# PSUBoard.net
KiCad netlist of a schematic drawn in EAGLE
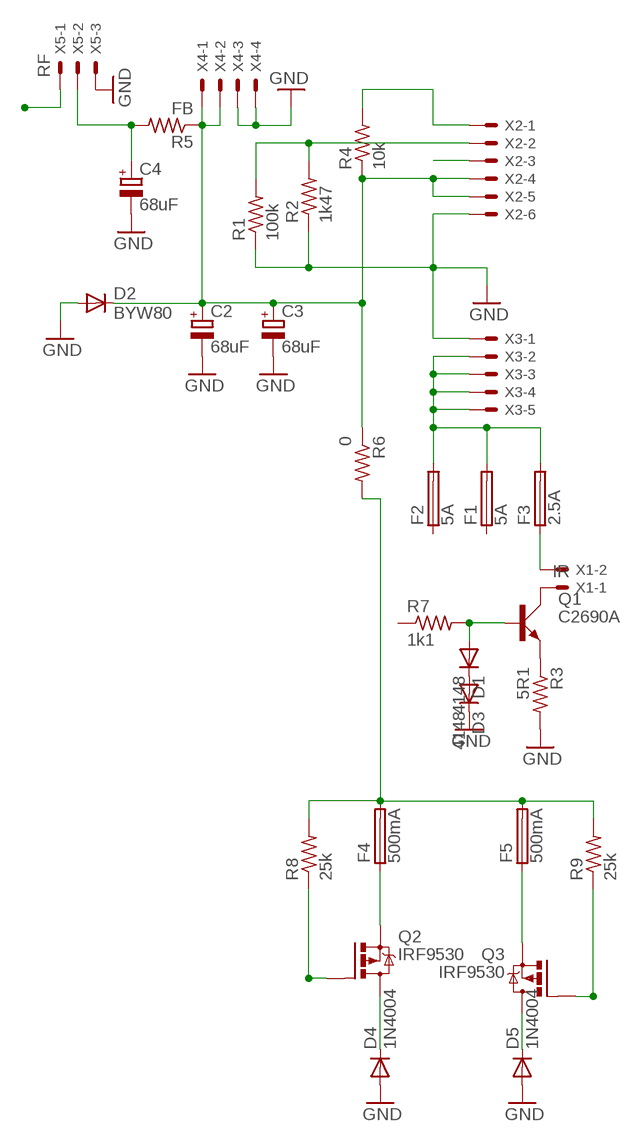
[diagram p0: schematic, sheet 1]

(export (version "E")
  (design (tool "Eeschema 10.0.6"))
  (components
    (comp (ref "C2")
      (value "68uF")
      (footprint "eagle-import:E3,5-10")
      (libsource (lib "eagle-import") (part "CPOL-EUE3.5-10"))
    )
    (comp (ref "C3")
      (value "68uF")
      (footprint "eagle-import:E3,5-10")
      (libsource (lib "eagle-import") (part "CPOL-EUE3.5-10"))
    )
    (comp (ref "C4")
      (value "68uF")
      (footprint "eagle-import:E3,5-10")
      (libsource (lib "eagle-import") (part "CPOL-EUE3.5-10"))
    )
    (comp (ref "D1")
      (value "4148")
      (footprint "eagle-import:DO35-7")
      (libsource (lib "eagle-import") (part "1N4148DO35-7"))
    )
    (comp (ref "D2")
      (value "BYW80")
      (footprint "eagle-import:TO220ACS")
      (libsource (lib "eagle-import") (part "BYW80"))
    )
    (comp (ref "D3")
      (value "4148")
      (footprint "eagle-import:DO35-7")
      (libsource (lib "eagle-import") (part "1N4148DO35-7"))
    )
    (comp (ref "D4")
      (value "1N4004")
      (footprint "eagle-import:DO41-10")
      (libsource (lib "eagle-import") (part "1N4004"))
    )
    (comp (ref "D5")
      (value "1N4004")
      (footprint "eagle-import:DO41-10")
      (libsource (lib "eagle-import") (part "1N4004"))
    )
    (comp (ref "F1")
      (value "5A")
      (footprint "eagle-import:TR5")
      (libsource (lib "eagle-import") (part "TR5"))
    )
    (comp (ref "F2")
      (value "5A")
      (footprint "eagle-import:TR5")
      (libsource (lib "eagle-import") (part "TR5"))
    )
    (comp (ref "F3")
      (value "2.5A")
      (footprint "eagle-import:TR5")
      (libsource (lib "eagle-import") (part "TR5"))
    )
    (comp (ref "F4")
      (value "500mA")
      (footprint "eagle-import:TR5")
      (libsource (lib "eagle-import") (part "TR5"))
    )
    (comp (ref "F5")
      (value "500mA")
      (footprint "eagle-import:TR5")
      (libsource (lib "eagle-import") (part "TR5"))
    )
    (comp (ref "Q1")
      (value "C2690A")
      (footprint "eagle-import:TO126AV")
      (libsource (lib "eagle-import") (part "BD139"))
    )
    (comp (ref "Q2")
      (value "IRF9530")
      (footprint "eagle-import:TO220BV")
      (libsource (lib "eagle-import") (part "IRF9530"))
    )
    (comp (ref "Q3")
      (value "IRF9530")
      (footprint "eagle-import:TO220BV")
      (libsource (lib "eagle-import") (part "IRF9530"))
    )
    (comp (ref "R1")
      (value "100k")
      (footprint "eagle-import:0309_12")
      (libsource (lib "eagle-import") (part "R-US_0309/12"))
    )
    (comp (ref "R2")
      (value "1k47")
      (footprint "eagle-import:0617_22")
      (libsource (lib "eagle-import") (part "R-US_0617/22"))
    )
    (comp (ref "R3")
      (value "5R1")
      (footprint "eagle-import:0309_10")
      (libsource (lib "eagle-import") (part "R-US_0309/10"))
    )
    (comp (ref "R4")
      (value "10k")
      (footprint "eagle-import:0309_12")
      (libsource (lib "eagle-import") (part "R-US_0309/12"))
    )
    (comp (ref "R5")
      (value "FB")
      (footprint "eagle-import:0309_12")
      (libsource (lib "eagle-import") (part "R-US_0309/12"))
    )
    (comp (ref "R6")
      (value "0")
      (footprint "eagle-import:0309_12")
      (libsource (lib "eagle-import") (part "R-US_0309/12"))
    )
    (comp (ref "R7")
      (value "1k1")
      (footprint "eagle-import:0309_10")
      (libsource (lib "eagle-import") (part "R-US_0309/10"))
    )
    (comp (ref "R8")
      (value "25k")
      (footprint "eagle-import:0309_10")
      (libsource (lib "eagle-import") (part "R-US_0309/10"))
    )
    (comp (ref "R9")
      (value "25k")
      (footprint "eagle-import:0309_10")
      (libsource (lib "eagle-import") (part "R-US_0309/10"))
    )
    (comp (ref "X1")
      (value "IR")
      (footprint "eagle-import:22-23-2021")
      (fields (field (name "MF") "MOLEX") (field (name "MPN") "22-23-2021"))
      (libsource (lib "eagle-import") (part "22-23-2021"))
    )
    (comp (ref "X2")
      (value "22-23-2061")
      (footprint "eagle-import:22-23-2061")
      (fields (field (name "MF") "MOLEX"))
      (libsource (lib "eagle-import") (part "22-23-2061"))
    )
    (comp (ref "X3")
      (value "22-23-2051")
      (footprint "eagle-import:22-23-2051")
      (fields (field (name "MF") "MOLEX"))
      (libsource (lib "eagle-import") (part "22-23-2051"))
    )
    (comp (ref "X4")
      (value "22-23-2041")
      (footprint "eagle-import:22-23-2041")
      (fields (field (name "MF") "MOLEX"))
      (libsource (lib "eagle-import") (part "22-23-2041"))
    )
    (comp (ref "X5")
      (value "RF")
      (footprint "eagle-import:22-23-2031")
      (fields (field (name "MF") "MOLEX") (field (name "MPN") "22-23-2031"))
      (libsource (lib "eagle-import") (part "22-23-2031"))
    )
  )
  (nets
    (net (code "1") (name "GND") (class "Default")
      (node (ref "C2") (pin "-") (pinfunction "-_-") (pintype "passive"))
      (node (ref "C3") (pin "-") (pinfunction "-_-") (pintype "passive"))
      (node (ref "C4") (pin "-") (pinfunction "-_-") (pintype "passive"))
      (node (ref "D2") (pin "A") (pinfunction "A_A") (pintype "passive"))
      (node (ref "D3") (pin "C") (pinfunction "C_C") (pintype "passive"))
      (node (ref "D4") (pin "A") (pinfunction "A_A") (pintype "passive"))
      (node (ref "D5") (pin "A") (pinfunction "A_A") (pintype "passive"))
      (node (ref "R1") (pin "1") (pinfunction "1_1") (pintype "passive"))
      (node (ref "R2") (pin "1") (pinfunction "1_1") (pintype "passive"))
      (node (ref "R3") (pin "2") (pinfunction "2_2") (pintype "passive"))
      (node (ref "X2") (pin "6") (pinfunction "S_6") (pintype "passive"))
      (node (ref "X3") (pin "1") (pinfunction "S_1") (pintype "passive"))
      (node (ref "X4") (pin "3") (pinfunction "S_3") (pintype "passive"))
      (node (ref "X4") (pin "4") (pinfunction "S_4") (pintype "passive"))
      (node (ref "X5") (pin "3") (pinfunction "S_3") (pintype "passive"))
    )
    (net (code "2") (name "Net-(D1-PadA)") (class "Default")
      (node (ref "D1") (pin "A") (pinfunction "A_A") (pintype "passive"))
      (node (ref "Q1") (pin "B") (pinfunction "B_B") (pintype "passive"))
      (node (ref "R7") (pin "2") (pinfunction "2_2") (pintype "passive"))
    )
    (net (code "3") (name "Net-(D1-PadC)") (class "Default")
      (node (ref "D1") (pin "C") (pinfunction "C_C") (pintype "passive"))
      (node (ref "D3") (pin "A") (pinfunction "A_A") (pintype "passive"))
    )
    (net (code "4") (name "Net-(D4-PadC)") (class "Default")
      (node (ref "D4") (pin "C") (pinfunction "C_C") (pintype "passive"))
      (node (ref "Q2") (pin "D") (pinfunction "D_D") (pintype "passive"))
    )
    (net (code "5") (name "Net-(D5-PadC)") (class "Default")
      (node (ref "D5") (pin "C") (pinfunction "C_C") (pintype "passive"))
      (node (ref "Q3") (pin "D") (pinfunction "D_D") (pintype "passive"))
    )
    (net (code "6") (name "Net-(F4-Pad1)") (class "Default")
      (node (ref "F4") (pin "1") (pinfunction "1_1") (pintype "passive"))
      (node (ref "Q2") (pin "S") (pinfunction "S_S") (pintype "passive"))
    )
    (net (code "7") (name "Net-(F4-Pad2)") (class "Default")
      (node (ref "F4") (pin "2") (pinfunction "2_2") (pintype "passive"))
      (node (ref "F5") (pin "2") (pinfunction "2_2") (pintype "passive"))
      (node (ref "R6") (pin "2") (pinfunction "2_2") (pintype "passive"))
      (node (ref "R8") (pin "2") (pinfunction "2_2") (pintype "passive"))
      (node (ref "R9") (pin "2") (pinfunction "2_2") (pintype "passive"))
    )
    (net (code "8") (name "Net-(F5-Pad1)") (class "Default")
      (node (ref "F5") (pin "1") (pinfunction "1_1") (pintype "passive"))
      (node (ref "Q3") (pin "S") (pinfunction "S_S") (pintype "passive"))
    )
    (net (code "9") (name "Net-(Q1-PadE)") (class "Default")
      (node (ref "Q1") (pin "E") (pinfunction "E_E") (pintype "passive"))
      (node (ref "R3") (pin "1") (pinfunction "1_1") (pintype "passive"))
    )
    (net (code "10") (name "Net-(Q2-PadG)") (class "Default")
      (node (ref "Q2") (pin "G") (pinfunction "G_G") (pintype "passive"))
      (node (ref "R8") (pin "1") (pinfunction "1_1") (pintype "passive"))
    )
    (net (code "11") (name "Net-(Q3-PadG)") (class "Default")
      (node (ref "Q3") (pin "G") (pinfunction "G_G") (pintype "passive"))
      (node (ref "R9") (pin "1") (pinfunction "1_1") (pintype "passive"))
    )
    (net (code "12") (name "Net-(X1A-S)") (class "Default")
      (node (ref "Q1") (pin "C") (pinfunction "C_C") (pintype "passive"))
      (node (ref "X1") (pin "1") (pinfunction "S_1") (pintype "passive"))
    )
    (net (code "13") (name "Net-(X1B-S)") (class "Default")
      (node (ref "F3") (pin "1") (pinfunction "1_1") (pintype "passive"))
      (node (ref "X1") (pin "2") (pinfunction "S_2") (pintype "passive"))
    )
    (net (code "14") (name "Net-(X2A-S)") (class "Default")
      (node (ref "R4") (pin "2") (pinfunction "2_2") (pintype "passive"))
      (node (ref "X2") (pin "1") (pinfunction "S_1") (pintype "passive"))
    )
    (net (code "15") (name "Net-(X2B-S)") (class "Default")
      (node (ref "R1") (pin "2") (pinfunction "2_2") (pintype "passive"))
      (node (ref "R2") (pin "2") (pinfunction "2_2") (pintype "passive"))
      (node (ref "X2") (pin "2") (pinfunction "S_2") (pintype "passive"))
    )
    (net (code "16") (name "Net-(X2D-S)") (class "Default")
      (node (ref "C2") (pin "+") (pinfunction "+_+") (pintype "passive"))
      (node (ref "C3") (pin "+") (pinfunction "+_+") (pintype "passive"))
      (node (ref "D2") (pin "C") (pinfunction "C_C") (pintype "passive"))
      (node (ref "R4") (pin "1") (pinfunction "1_1") (pintype "passive"))
      (node (ref "R5") (pin "1") (pinfunction "1_1") (pintype "passive"))
      (node (ref "R6") (pin "1") (pinfunction "1_1") (pintype "passive"))
      (node (ref "X2") (pin "4") (pinfunction "S_4") (pintype "passive"))
      (node (ref "X2") (pin "5") (pinfunction "S_5") (pintype "passive"))
      (node (ref "X4") (pin "1") (pinfunction "S_1") (pintype "passive"))
      (node (ref "X4") (pin "2") (pinfunction "S_2") (pintype "passive"))
    )
    (net (code "17") (name "Net-(X3B-S)") (class "Default")
      (node (ref "F1") (pin "2") (pinfunction "2_2") (pintype "passive"))
      (node (ref "F2") (pin "2") (pinfunction "2_2") (pintype "passive"))
      (node (ref "F3") (pin "2") (pinfunction "2_2") (pintype "passive"))
      (node (ref "X3") (pin "2") (pinfunction "S_2") (pintype "passive"))
      (node (ref "X3") (pin "3") (pinfunction "S_3") (pintype "passive"))
      (node (ref "X3") (pin "4") (pinfunction "S_4") (pintype "passive"))
      (node (ref "X3") (pin "5") (pinfunction "S_5") (pintype "passive"))
    )
    (net (code "18") (name "Net-(X5B-S)") (class "Default")
      (node (ref "C4") (pin "+") (pinfunction "+_+") (pintype "passive"))
      (node (ref "R5") (pin "2") (pinfunction "2_2") (pintype "passive"))
      (node (ref "X5") (pin "2") (pinfunction "S_2") (pintype "passive"))
    )
    (net (code "19") (name "unconnected-(F1-Pad1)") (class "Default")
      (node (ref "F1") (pin "1") (pinfunction "1_1") (pintype "passive"))
    )
    (net (code "20") (name "unconnected-(F2-Pad1)") (class "Default")
      (node (ref "F2") (pin "1") (pinfunction "1_1") (pintype "passive"))
    )
    (net (code "21") (name "unconnected-(R7-Pad1)") (class "Default")
      (node (ref "R7") (pin "1") (pinfunction "1_1") (pintype "passive"))
    )
    (net (code "22") (name "unconnected-(X2C-S-Pad3)") (class "Default")
      (node (ref "X2") (pin "3") (pinfunction "S_3") (pintype "passive"))
    )
    (net (code "23") (name "unconnected-(X5A-S-Pad1)") (class "Default")
      (node (ref "X5") (pin "1") (pinfunction "S_1") (pintype "passive"))
    )
  )
)
